# Lab_3_-_Bluetooth_BM20_Breakout.net
KiCad netlist of a schematic drawn in EAGLE
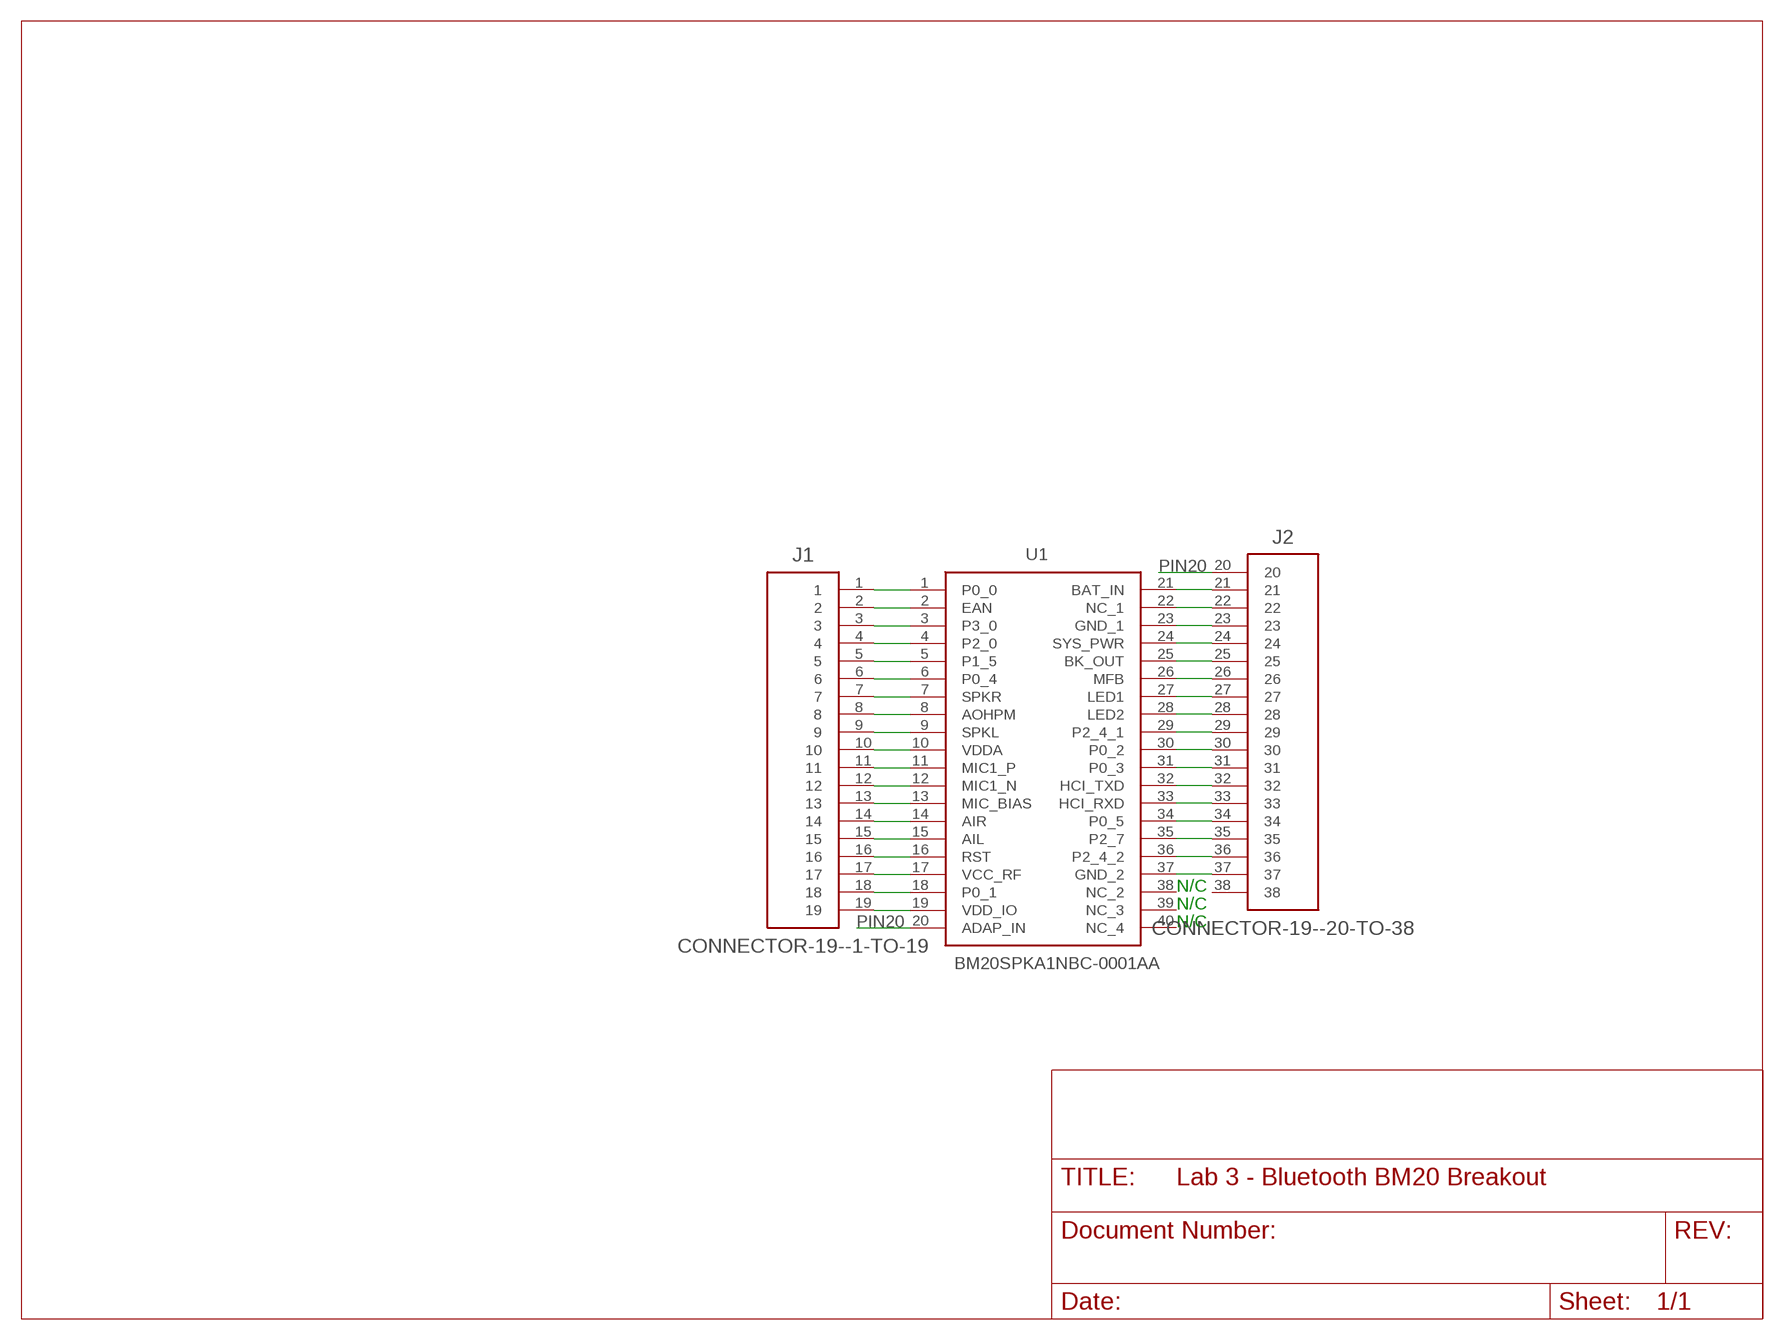
[diagram p0: schematic, sheet 1]

(export (version "E")
  (design (tool "Eeschema 10.0.6"))
  (components
    (comp (ref "J1")
      (value "CONNECTOR-19--1-TO-19")
      (footprint "eagle-import:ESQ-119-XX-XX-S")
      (libsource (lib "eagle-import") (part "CONNECTOR-19--1-TO-19"))
    )
    (comp (ref "J2")
      (value "CONNECTOR-19--20-TO-38")
      (footprint "eagle-import:ESQ-119-XX-XX-S--PIN-1-ROUND")
      (libsource (lib "eagle-import") (part "CONNECTOR-19--20-TO-38"))
    )
    (comp (ref "U1")
      (value "BM20SPKA1NBC-0001AA")
      (footprint "eagle-import:BM20SPKA1NBC0001AA")
      (fields (field (name "MOUSER_PART_NUMBER") "579-SPKA1NBC-0001AA"))
      (libsource (lib "eagle-import") (part "BM20SPKA1NBC-0001AA"))
    )
  )
  (nets
    (net (code "1") (name "/PIN20") (class "Default")
      (node (ref "J2") (pin "20") (pinfunction "20_20") (pintype "bidirectional"))
      (node (ref "U1") (pin "20") (pinfunction "ADAP_IN_20") (pintype "bidirectional"))
    )
    (net (code "2") (name "Net-(U1-AIL)") (class "Default")
      (node (ref "J1") (pin "15") (pinfunction "15_15") (pintype "bidirectional"))
      (node (ref "U1") (pin "15") (pinfunction "AIL_15") (pintype "bidirectional"))
    )
    (net (code "3") (name "Net-(U1-AIR)") (class "Default")
      (node (ref "J1") (pin "14") (pinfunction "14_14") (pintype "bidirectional"))
      (node (ref "U1") (pin "14") (pinfunction "AIR_14") (pintype "bidirectional"))
    )
    (net (code "4") (name "Net-(U1-AOHPM)") (class "Default")
      (node (ref "J1") (pin "8") (pinfunction "8_8") (pintype "bidirectional"))
      (node (ref "U1") (pin "8") (pinfunction "AOHPM_8") (pintype "bidirectional"))
    )
    (net (code "5") (name "Net-(U1-BAT_IN)") (class "Default")
      (node (ref "J2") (pin "21") (pinfunction "21_21") (pintype "bidirectional"))
      (node (ref "U1") (pin "21") (pinfunction "BAT_IN_21") (pintype "bidirectional"))
    )
    (net (code "6") (name "Net-(U1-BK_OUT)") (class "Default")
      (node (ref "J2") (pin "25") (pinfunction "25_25") (pintype "bidirectional"))
      (node (ref "U1") (pin "25") (pinfunction "BK_OUT_25") (pintype "bidirectional"))
    )
    (net (code "7") (name "Net-(U1-EAN)") (class "Default")
      (node (ref "J1") (pin "2") (pinfunction "2_2") (pintype "bidirectional"))
      (node (ref "U1") (pin "2") (pinfunction "EAN_2") (pintype "bidirectional"))
    )
    (net (code "8") (name "Net-(U1-GND_1)") (class "Default")
      (node (ref "J2") (pin "23") (pinfunction "23_23") (pintype "bidirectional"))
      (node (ref "U1") (pin "23") (pinfunction "GND_1_23") (pintype "bidirectional"))
    )
    (net (code "9") (name "Net-(U1-GND_2)") (class "Default")
      (node (ref "J2") (pin "37") (pinfunction "37_37") (pintype "bidirectional"))
      (node (ref "U1") (pin "37") (pinfunction "GND_2_37") (pintype "bidirectional"))
    )
    (net (code "10") (name "Net-(U1-HCI_RXD)") (class "Default")
      (node (ref "J2") (pin "33") (pinfunction "33_33") (pintype "bidirectional"))
      (node (ref "U1") (pin "33") (pinfunction "HCI_RXD_33") (pintype "bidirectional"))
    )
    (net (code "11") (name "Net-(U1-HCI_TXD)") (class "Default")
      (node (ref "J2") (pin "32") (pinfunction "32_32") (pintype "bidirectional"))
      (node (ref "U1") (pin "32") (pinfunction "HCI_TXD_32") (pintype "bidirectional"))
    )
    (net (code "12") (name "Net-(U1-LED1)") (class "Default")
      (node (ref "J2") (pin "27") (pinfunction "27_27") (pintype "bidirectional"))
      (node (ref "U1") (pin "27") (pinfunction "LED1_27") (pintype "bidirectional"))
    )
    (net (code "13") (name "Net-(U1-LED2)") (class "Default")
      (node (ref "J2") (pin "28") (pinfunction "28_28") (pintype "bidirectional"))
      (node (ref "U1") (pin "28") (pinfunction "LED2_28") (pintype "bidirectional"))
    )
    (net (code "14") (name "Net-(U1-MFB)") (class "Default")
      (node (ref "J2") (pin "26") (pinfunction "26_26") (pintype "bidirectional"))
      (node (ref "U1") (pin "26") (pinfunction "MFB_26") (pintype "bidirectional"))
    )
    (net (code "15") (name "Net-(U1-MIC1_N)") (class "Default")
      (node (ref "J1") (pin "12") (pinfunction "12_12") (pintype "bidirectional"))
      (node (ref "U1") (pin "12") (pinfunction "MIC1_N_12") (pintype "bidirectional"))
    )
    (net (code "16") (name "Net-(U1-MIC1_P)") (class "Default")
      (node (ref "J1") (pin "11") (pinfunction "11_11") (pintype "bidirectional"))
      (node (ref "U1") (pin "11") (pinfunction "MIC1_P_11") (pintype "bidirectional"))
    )
    (net (code "17") (name "Net-(U1-MIC_BIAS)") (class "Default")
      (node (ref "J1") (pin "13") (pinfunction "13_13") (pintype "bidirectional"))
      (node (ref "U1") (pin "13") (pinfunction "MIC_BIAS_13") (pintype "bidirectional"))
    )
    (net (code "18") (name "Net-(U1-NC_1)") (class "Default")
      (node (ref "J2") (pin "22") (pinfunction "22_22") (pintype "bidirectional"))
      (node (ref "U1") (pin "22") (pinfunction "NC_1_22") (pintype "bidirectional"))
    )
    (net (code "19") (name "Net-(U1-P0_0)") (class "Default")
      (node (ref "J1") (pin "1") (pinfunction "1_1") (pintype "bidirectional"))
      (node (ref "U1") (pin "1") (pinfunction "P0_0_1") (pintype "bidirectional"))
    )
    (net (code "20") (name "Net-(U1-P0_1)") (class "Default")
      (node (ref "J1") (pin "18") (pinfunction "18_18") (pintype "bidirectional"))
      (node (ref "U1") (pin "18") (pinfunction "P0_1_18") (pintype "bidirectional"))
    )
    (net (code "21") (name "Net-(U1-P0_2)") (class "Default")
      (node (ref "J2") (pin "30") (pinfunction "30_30") (pintype "bidirectional"))
      (node (ref "U1") (pin "30") (pinfunction "P0_2_30") (pintype "bidirectional"))
    )
    (net (code "22") (name "Net-(U1-P0_3)") (class "Default")
      (node (ref "J2") (pin "31") (pinfunction "31_31") (pintype "bidirectional"))
      (node (ref "U1") (pin "31") (pinfunction "P0_3_31") (pintype "bidirectional"))
    )
    (net (code "23") (name "Net-(U1-P0_4)") (class "Default")
      (node (ref "J1") (pin "6") (pinfunction "6_6") (pintype "bidirectional"))
      (node (ref "U1") (pin "6") (pinfunction "P0_4_6") (pintype "bidirectional"))
    )
    (net (code "24") (name "Net-(U1-P0_5)") (class "Default")
      (node (ref "J2") (pin "34") (pinfunction "34_34") (pintype "bidirectional"))
      (node (ref "U1") (pin "34") (pinfunction "P0_5_34") (pintype "bidirectional"))
    )
    (net (code "25") (name "Net-(U1-P1_5)") (class "Default")
      (node (ref "J1") (pin "5") (pinfunction "5_5") (pintype "bidirectional"))
      (node (ref "U1") (pin "5") (pinfunction "P1_5_5") (pintype "bidirectional"))
    )
    (net (code "26") (name "Net-(U1-P2_0)") (class "Default")
      (node (ref "J1") (pin "4") (pinfunction "4_4") (pintype "bidirectional"))
      (node (ref "U1") (pin "4") (pinfunction "P2_0_4") (pintype "bidirectional"))
    )
    (net (code "27") (name "Net-(U1-P2_4_1)") (class "Default")
      (node (ref "J2") (pin "29") (pinfunction "29_29") (pintype "bidirectional"))
      (node (ref "U1") (pin "29") (pinfunction "P2_4_1_29") (pintype "bidirectional"))
    )
    (net (code "28") (name "Net-(U1-P2_4_2)") (class "Default")
      (node (ref "J2") (pin "36") (pinfunction "36_36") (pintype "bidirectional"))
      (node (ref "U1") (pin "36") (pinfunction "P2_4_2_36") (pintype "bidirectional"))
    )
    (net (code "29") (name "Net-(U1-P2_7)") (class "Default")
      (node (ref "J2") (pin "35") (pinfunction "35_35") (pintype "bidirectional"))
      (node (ref "U1") (pin "35") (pinfunction "P2_7_35") (pintype "bidirectional"))
    )
    (net (code "30") (name "Net-(U1-P3_0)") (class "Default")
      (node (ref "J1") (pin "3") (pinfunction "3_3") (pintype "bidirectional"))
      (node (ref "U1") (pin "3") (pinfunction "P3_0_3") (pintype "bidirectional"))
    )
    (net (code "31") (name "Net-(U1-RST)") (class "Default")
      (node (ref "J1") (pin "16") (pinfunction "16_16") (pintype "bidirectional"))
      (node (ref "U1") (pin "16") (pinfunction "RST_16") (pintype "bidirectional"))
    )
    (net (code "32") (name "Net-(U1-SPKL)") (class "Default")
      (node (ref "J1") (pin "9") (pinfunction "9_9") (pintype "bidirectional"))
      (node (ref "U1") (pin "9") (pinfunction "SPKL_9") (pintype "bidirectional"))
    )
    (net (code "33") (name "Net-(U1-SPKR)") (class "Default")
      (node (ref "J1") (pin "7") (pinfunction "7_7") (pintype "bidirectional"))
      (node (ref "U1") (pin "7") (pinfunction "SPKR_7") (pintype "bidirectional"))
    )
    (net (code "34") (name "Net-(U1-SYS_PWR)") (class "Default")
      (node (ref "J2") (pin "24") (pinfunction "24_24") (pintype "bidirectional"))
      (node (ref "U1") (pin "24") (pinfunction "SYS_PWR_24") (pintype "bidirectional"))
    )
    (net (code "35") (name "Net-(U1-VCC_RF)") (class "Default")
      (node (ref "J1") (pin "17") (pinfunction "17_17") (pintype "bidirectional"))
      (node (ref "U1") (pin "17") (pinfunction "VCC_RF_17") (pintype "bidirectional"))
    )
    (net (code "36") (name "Net-(U1-VDDA)") (class "Default")
      (node (ref "J1") (pin "10") (pinfunction "10_10") (pintype "bidirectional"))
      (node (ref "U1") (pin "10") (pinfunction "VDDA_10") (pintype "bidirectional"))
    )
    (net (code "37") (name "Net-(U1-VDD_IO)") (class "Default")
      (node (ref "J1") (pin "19") (pinfunction "19_19") (pintype "bidirectional"))
      (node (ref "U1") (pin "19") (pinfunction "VDD_IO_19") (pintype "bidirectional"))
    )
    (net (code "38") (name "unconnected-(J2-Pad38)") (class "Default")
      (node (ref "J2") (pin "38") (pinfunction "38_38") (pintype "bidirectional"))
    )
    (net (code "39") (name "unconnected-(U1-NC_2-Pad38)") (class "Default")
      (node (ref "U1") (pin "38") (pinfunction "NC_2_38") (pintype "bidirectional"))
    )
    (net (code "40") (name "unconnected-(U1-NC_3-Pad39)") (class "Default")
      (node (ref "U1") (pin "39") (pinfunction "NC_3_39") (pintype "bidirectional"))
    )
    (net (code "41") (name "unconnected-(U1-NC_4-Pad40)") (class "Default")
      (node (ref "U1") (pin "40") (pinfunction "NC_4_40") (pintype "bidirectional"))
    )
  )
)
